# sd_card.net
KiCad netlist of a schematic drawn in Altium Designer
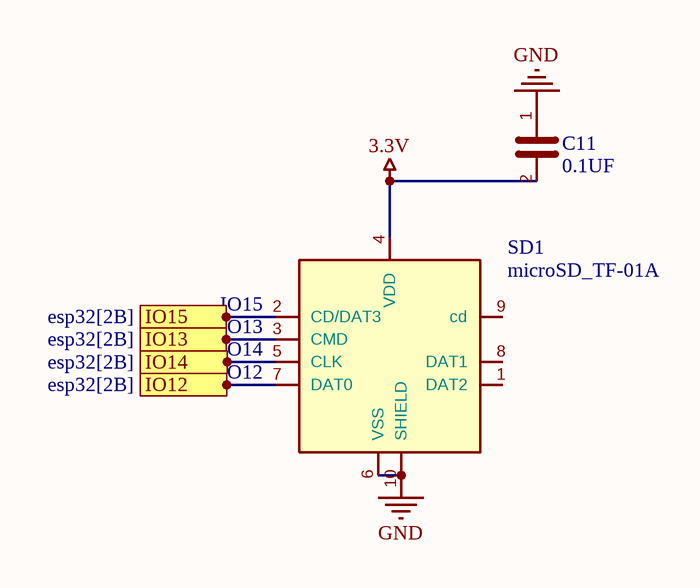
[diagram p0: sd_card.SchDoc]

(export (version "E")
  (design (tool "Eeschema 10.0.6"))
  (components
    (comp (ref "C11")
      (value "0.1UF")
      (footprint "CAPC2013X70X45NL10T25")
      (libsource (lib "Thermal_Camera") (part "C"))
    )
    (comp (ref "SD1")
      (value "microSD_TF-01A")
      (footprint "TF-01A")
      (libsource (lib "Thermal_Camera") (part "microSD_TF-01A"))
    )
  )
  (nets
    (net (code "1") (name "/IO12") (class "Default")
      (node (ref "SD1") (pin "7") (pinfunction "DAT0_7") (pintype "passive"))
    )
    (net (code "2") (name "/IO13") (class "Default")
      (node (ref "SD1") (pin "3") (pinfunction "CMD_3") (pintype "passive"))
    )
    (net (code "3") (name "/IO14") (class "Default")
      (node (ref "SD1") (pin "5") (pinfunction "CLK_5") (pintype "passive"))
    )
    (net (code "4") (name "/IO15") (class "Default")
      (node (ref "SD1") (pin "2") (pinfunction "CD/DAT3_2") (pintype "passive"))
    )
    (net (code "5") (name "3.3V") (class "Default")
      (node (ref "C11") (pin "2") (pinfunction "2_2") (pintype "passive"))
      (node (ref "SD1") (pin "4") (pinfunction "VDD_4") (pintype "passive"))
    )
    (net (code "6") (name "GND") (class "Default")
      (node (ref "C11") (pin "1") (pinfunction "1_1") (pintype "passive"))
      (node (ref "SD1") (pin "10") (pinfunction "SHIELD_10") (pintype "passive"))
      (node (ref "SD1") (pin "6") (pinfunction "VSS_6") (pintype "passive"))
    )
    (net (code "7") (name "unconnected-(SD1-DAT1-Pad8)") (class "Default")
      (node (ref "SD1") (pin "8") (pinfunction "DAT1_8") (pintype "passive"))
    )
    (net (code "8") (name "unconnected-(SD1-DAT2-Pad1)") (class "Default")
      (node (ref "SD1") (pin "1") (pinfunction "DAT2_1") (pintype "passive"))
    )
    (net (code "9") (name "unconnected-(SD1-cd-Pad9)") (class "Default")
      (node (ref "SD1") (pin "9") (pinfunction "cd_9") (pintype "passive"))
    )
  )
)
